# I2C_TH_Sensor_Socket.net
KiCad netlist of a schematic drawn in Altium Designer
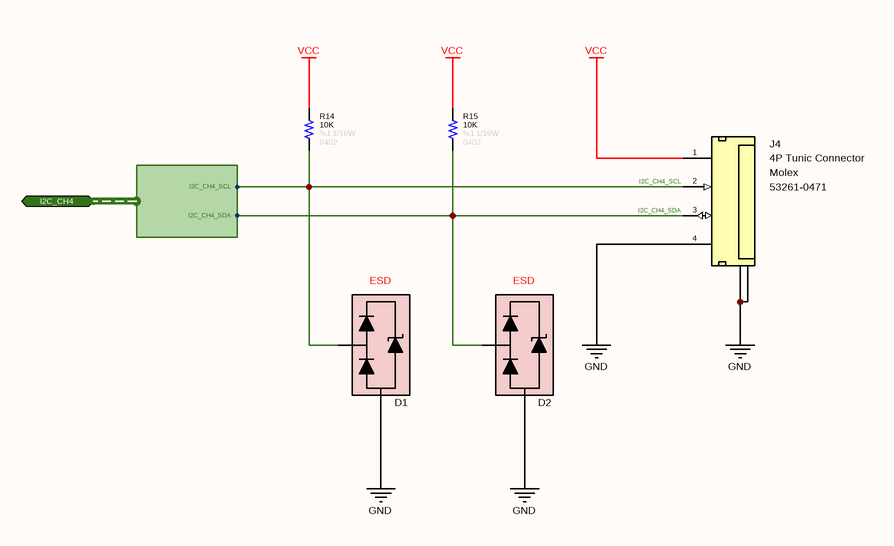
[diagram p0: I2C TH Sensor Socket.SchDoc]

(export (version "E")
  (design (tool "Eeschema 10.0.6"))
  (components
    (comp (ref "D1")
      (value "0402ESDA-MLP1")
      (footprint "ESD_0402")
      (description "SUPPRESSOR ESD 30VDC 0402 HFREE")
      (libsource (lib "P101DA_Library") (part "Diode - TPD1E05U06DPYR"))
    )
    (comp (ref "D2")
      (value "0402ESDA-MLP1")
      (footprint "ESD_0402")
      (description "SUPPRESSOR ESD 30VDC 0402 HFREE")
      (libsource (lib "P101DA_Library") (part "Diode - TPD1E05U06DPYR"))
    )
    (comp (ref "J4")
      (value "4P SMD Tunic Connector")
      (footprint "Connector_Tunic 4P")
      (description "Mini Tunic Connector with 4P")
      (fields
        (field (name "MANUFACTURER NAME") "Molex")
        (field (name "MANUFACTURER PART NUMBER") "53261-0471")
      )
      (libsource (lib "P101DA_Library") (part "Connector - Mini Tunic 4P (1.25)"))
    )
    (comp (ref "R14")
      (value "10K")
      (footprint "RESISTOR_0402")
      (description "Thick Film Resistors - SMD 1/16 W 10 KOhm 1%")
      (fields
        (field (name "MANUFACTURER PART NUMBER") "CRCW040210K0FKED")
        (field (name "TOLERANCE") "%1")
        (field (name "CASE") "0402")
        (field (name "POWER") "1/16W")
        (field (name "Comment") "10K - 0402 - %1 - 1/16W")
      )
      (libsource (lib "P101DA_Library") (part "Resistor - 10K [0402]"))
    )
    (comp (ref "R15")
      (value "10K")
      (footprint "RESISTOR_0402")
      (description "Thick Film Resistors - SMD 1/16 W 10 KOhm 1%")
      (fields
        (field (name "MANUFACTURER PART NUMBER") "CRCW040210K0FKED")
        (field (name "TOLERANCE") "%1")
        (field (name "CASE") "0402")
        (field (name "POWER") "1/16W")
        (field (name "Comment") "10K - 0402 - %1 - 1/16W")
      )
      (libsource (lib "P101DA_Library") (part "Resistor - 10K [0402]"))
    )
  )
  (nets
    (net (code "2") (name "/I2C_CH4_SCL") (class "Default")
      (node (ref "D1") (pin "1") (pinfunction "I/O_1") (pintype "passive"))
      (node (ref "J4") (pin "2") (pinfunction "Pin-2_2") (pintype "input"))
      (node (ref "R14") (pin "1") (pinfunction "1_1") (pintype "passive"))
    )
    (net (code "3") (name "/I2C_CH4_SDA") (class "Default")
      (node (ref "D2") (pin "1") (pinfunction "I/O_1") (pintype "passive"))
      (node (ref "J4") (pin "3") (pinfunction "Pin-3_3") (pintype "bidirectional"))
      (node (ref "R15") (pin "1") (pinfunction "1_1") (pintype "passive"))
    )
    (net (code "5") (name "GND") (class "Default")
      (node (ref "D1") (pin "2") (pinfunction "GND_2") (pintype "passive"))
      (node (ref "D2") (pin "2") (pinfunction "GND_2") (pintype "passive"))
      (node (ref "J4") (pin "4") (pinfunction "Pin-4_4") (pintype "passive"))
      (node (ref "J4") (pin "5") (pinfunction "GND_5") (pintype "passive"))
      (node (ref "J4") (pin "6") (pinfunction "GND_6") (pintype "passive"))
    )
    (net (code "6") (name "VCC") (class "Default")
      (node (ref "J4") (pin "1") (pinfunction "Pin-1_1") (pintype "passive"))
      (node (ref "R14") (pin "2") (pinfunction "2_2") (pintype "passive"))
      (node (ref "R15") (pin "2") (pinfunction "2_2") (pintype "passive"))
    )
  )
)
